# adapter.net
KiCad netlist of a schematic drawn in Altium Designer
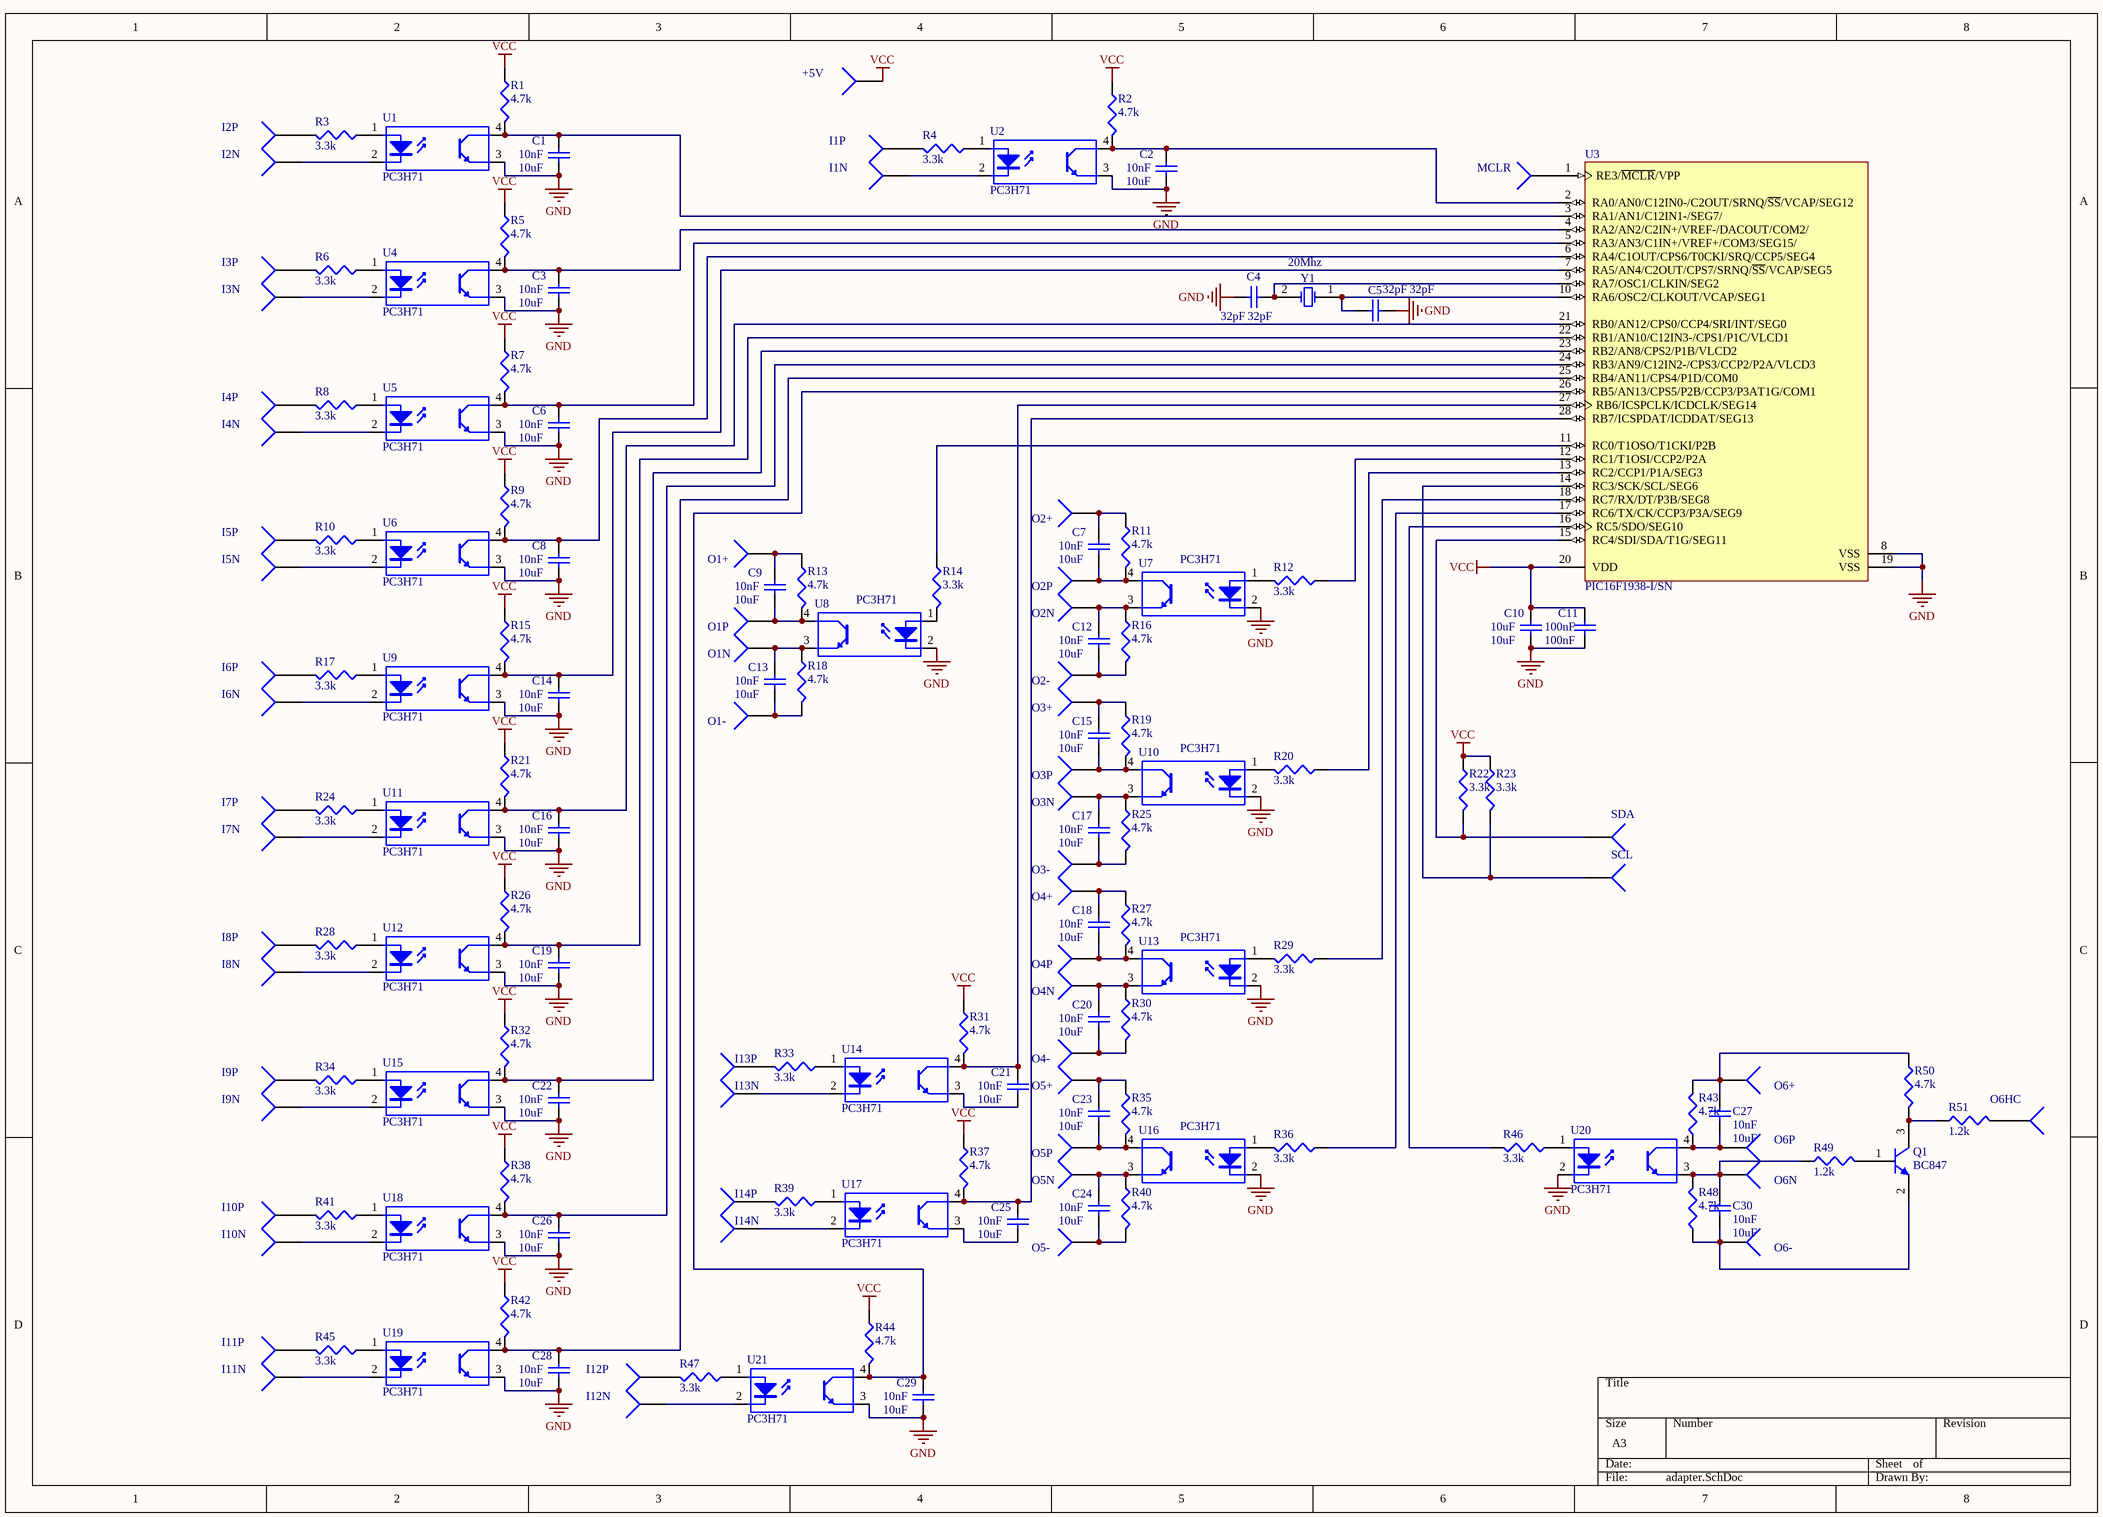
[diagram p0: adapter.SchDoc]

(export (version "E")
  (design (tool "Eeschema 10.0.6"))
  (components
    (comp (ref "+5V")
      (value "IN")
      (footprint "PIN1L")
      (description "Socket")
      (fields (field (name "PUBLISHER") "Altium Limited"))
      (libsource (lib "misc") (part "Socket"))
    )
    (comp (ref "C1")
      (value "10nF")
      (footprint "1608[0603]")
      (description "Capacitor")
      (fields (field (name "ALTIUM_VALUE") "10uF") (field (name "PUBLISHER") "Altium Limited"))
      (libsource (lib "Miscellaneous Devices") (part "Cap"))
    )
    (comp (ref "C2")
      (value "10nF")
      (footprint "1608[0603]")
      (description "Capacitor")
      (fields (field (name "ALTIUM_VALUE") "10uF") (field (name "PUBLISHER") "Altium Limited"))
      (libsource (lib "Miscellaneous Devices") (part "Cap"))
    )
    (comp (ref "C3")
      (value "10nF")
      (footprint "1608[0603]")
      (description "Capacitor")
      (fields (field (name "ALTIUM_VALUE") "10uF") (field (name "PUBLISHER") "Altium Limited"))
      (libsource (lib "Miscellaneous Devices") (part "Cap"))
    )
    (comp (ref "C4")
      (value "32pF")
      (footprint "1608[0603]")
      (description "Capacitor")
      (fields (field (name "ALTIUM_VALUE") "32pF") (field (name "PUBLISHER") "Altium Limited"))
      (libsource (lib "Miscellaneous Devices") (part "Cap"))
    )
    (comp (ref "C5")
      (value "32pF")
      (footprint "1608[0603]")
      (description "Capacitor")
      (fields (field (name "ALTIUM_VALUE") "32pF") (field (name "PUBLISHER") "Altium Limited"))
      (libsource (lib "Miscellaneous Devices") (part "Cap"))
    )
    (comp (ref "C6")
      (value "10nF")
      (footprint "1608[0603]")
      (description "Capacitor")
      (fields (field (name "ALTIUM_VALUE") "10uF") (field (name "PUBLISHER") "Altium Limited"))
      (libsource (lib "Miscellaneous Devices") (part "Cap"))
    )
    (comp (ref "C7")
      (value "10nF")
      (footprint "1608[0603]")
      (description "Capacitor")
      (fields (field (name "ALTIUM_VALUE") "10uF") (field (name "PUBLISHER") "Altium Limited"))
      (libsource (lib "Miscellaneous Devices") (part "Cap"))
    )
    (comp (ref "C8")
      (value "10nF")
      (footprint "1608[0603]")
      (description "Capacitor")
      (fields (field (name "ALTIUM_VALUE") "10uF") (field (name "PUBLISHER") "Altium Limited"))
      (libsource (lib "Miscellaneous Devices") (part "Cap"))
    )
    (comp (ref "C9")
      (value "10nF")
      (footprint "1608[0603]")
      (description "Capacitor")
      (fields (field (name "ALTIUM_VALUE") "10uF") (field (name "PUBLISHER") "Altium Limited"))
      (libsource (lib "Miscellaneous Devices") (part "Cap"))
    )
    (comp (ref "C10")
      (value "10uF")
      (footprint "1608[0603]")
      (description "Capacitor")
      (fields (field (name "ALTIUM_VALUE") "10uF") (field (name "PUBLISHER") "Altium Limited"))
      (libsource (lib "Miscellaneous Devices") (part "Cap"))
    )
    (comp (ref "C11")
      (value "100nF")
      (footprint "1608[0603]")
      (description "Capacitor")
      (fields (field (name "ALTIUM_VALUE") "100nF") (field (name "PUBLISHER") "Altium Limited"))
      (libsource (lib "Miscellaneous Devices") (part "Cap"))
    )
    (comp (ref "C12")
      (value "10nF")
      (footprint "1608[0603]")
      (description "Capacitor")
      (fields (field (name "ALTIUM_VALUE") "10uF") (field (name "PUBLISHER") "Altium Limited"))
      (libsource (lib "Miscellaneous Devices") (part "Cap"))
    )
    (comp (ref "C13")
      (value "10nF")
      (footprint "1608[0603]")
      (description "Capacitor")
      (fields (field (name "ALTIUM_VALUE") "10uF") (field (name "PUBLISHER") "Altium Limited"))
      (libsource (lib "Miscellaneous Devices") (part "Cap"))
    )
    (comp (ref "C14")
      (value "10nF")
      (footprint "1608[0603]")
      (description "Capacitor")
      (fields (field (name "ALTIUM_VALUE") "10uF") (field (name "PUBLISHER") "Altium Limited"))
      (libsource (lib "Miscellaneous Devices") (part "Cap"))
    )
    (comp (ref "C15")
      (value "10nF")
      (footprint "1608[0603]")
      (description "Capacitor")
      (fields (field (name "ALTIUM_VALUE") "10uF") (field (name "PUBLISHER") "Altium Limited"))
      (libsource (lib "Miscellaneous Devices") (part "Cap"))
    )
    (comp (ref "C16")
      (value "10nF")
      (footprint "1608[0603]")
      (description "Capacitor")
      (fields (field (name "ALTIUM_VALUE") "10uF") (field (name "PUBLISHER") "Altium Limited"))
      (libsource (lib "Miscellaneous Devices") (part "Cap"))
    )
    (comp (ref "C17")
      (value "10nF")
      (footprint "1608[0603]")
      (description "Capacitor")
      (fields (field (name "ALTIUM_VALUE") "10uF") (field (name "PUBLISHER") "Altium Limited"))
      (libsource (lib "Miscellaneous Devices") (part "Cap"))
    )
    (comp (ref "C18")
      (value "10nF")
      (footprint "1608[0603]")
      (description "Capacitor")
      (fields (field (name "ALTIUM_VALUE") "10uF") (field (name "PUBLISHER") "Altium Limited"))
      (libsource (lib "Miscellaneous Devices") (part "Cap"))
    )
    (comp (ref "C19")
      (value "10nF")
      (footprint "1608[0603]")
      (description "Capacitor")
      (fields (field (name "ALTIUM_VALUE") "10uF") (field (name "PUBLISHER") "Altium Limited"))
      (libsource (lib "Miscellaneous Devices") (part "Cap"))
    )
    (comp (ref "C20")
      (value "10nF")
      (footprint "1608[0603]")
      (description "Capacitor")
      (fields (field (name "ALTIUM_VALUE") "10uF") (field (name "PUBLISHER") "Altium Limited"))
      (libsource (lib "Miscellaneous Devices") (part "Cap"))
    )
    (comp (ref "C21")
      (value "10nF")
      (footprint "1608[0603]")
      (description "Capacitor")
      (fields (field (name "ALTIUM_VALUE") "10uF") (field (name "PUBLISHER") "Altium Limited"))
      (libsource (lib "Miscellaneous Devices") (part "Cap"))
    )
    (comp (ref "C22")
      (value "10nF")
      (footprint "1608[0603]")
      (description "Capacitor")
      (fields (field (name "ALTIUM_VALUE") "10uF") (field (name "PUBLISHER") "Altium Limited"))
      (libsource (lib "Miscellaneous Devices") (part "Cap"))
    )
    (comp (ref "C23")
      (value "10nF")
      (footprint "1608[0603]")
      (description "Capacitor")
      (fields (field (name "ALTIUM_VALUE") "10uF") (field (name "PUBLISHER") "Altium Limited"))
      (libsource (lib "Miscellaneous Devices") (part "Cap"))
    )
    (comp (ref "C24")
      (value "10nF")
      (footprint "1608[0603]")
      (description "Capacitor")
      (fields (field (name "ALTIUM_VALUE") "10uF") (field (name "PUBLISHER") "Altium Limited"))
      (libsource (lib "Miscellaneous Devices") (part "Cap"))
    )
    (comp (ref "C25")
      (value "10nF")
      (footprint "1608[0603]")
      (description "Capacitor")
      (fields (field (name "ALTIUM_VALUE") "10uF") (field (name "PUBLISHER") "Altium Limited"))
      (libsource (lib "Miscellaneous Devices") (part "Cap"))
    )
    (comp (ref "C26")
      (value "10nF")
      (footprint "1608[0603]")
      (description "Capacitor")
      (fields (field (name "ALTIUM_VALUE") "10uF") (field (name "PUBLISHER") "Altium Limited"))
      (libsource (lib "Miscellaneous Devices") (part "Cap"))
    )
    (comp (ref "C27")
      (value "10nF")
      (footprint "1608[0603]")
      (description "Capacitor")
      (fields (field (name "ALTIUM_VALUE") "10uF") (field (name "PUBLISHER") "Altium Limited"))
      (libsource (lib "Miscellaneous Devices") (part "Cap"))
    )
    (comp (ref "C28")
      (value "10nF")
      (footprint "1608[0603]")
      (description "Capacitor")
      (fields (field (name "ALTIUM_VALUE") "10uF") (field (name "PUBLISHER") "Altium Limited"))
      (libsource (lib "Miscellaneous Devices") (part "Cap"))
    )
    (comp (ref "C29")
      (value "10nF")
      (footprint "1608[0603]")
      (description "Capacitor")
      (fields (field (name "ALTIUM_VALUE") "10uF") (field (name "PUBLISHER") "Altium Limited"))
      (libsource (lib "Miscellaneous Devices") (part "Cap"))
    )
    (comp (ref "C30")
      (value "10nF")
      (footprint "1608[0603]")
      (description "Capacitor")
      (fields (field (name "ALTIUM_VALUE") "10uF") (field (name "PUBLISHER") "Altium Limited"))
      (libsource (lib "Miscellaneous Devices") (part "Cap"))
    )
    (comp (ref "I1N")
      (value "IN")
      (footprint "PIN1L")
      (description "Socket")
      (fields (field (name "PUBLISHER") "Altium Limited"))
      (libsource (lib "misc") (part "Socket"))
    )
    (comp (ref "I1P")
      (value "IN")
      (footprint "PIN1L")
      (description "Socket")
      (fields (field (name "PUBLISHER") "Altium Limited"))
      (libsource (lib "misc") (part "Socket"))
    )
    (comp (ref "I2N")
      (value "IN")
      (footprint "PIN1L")
      (description "Socket")
      (fields (field (name "PUBLISHER") "Altium Limited"))
      (libsource (lib "misc") (part "Socket"))
    )
    (comp (ref "I2P")
      (value "IN")
      (footprint "PIN1L")
      (description "Socket")
      (fields (field (name "PUBLISHER") "Altium Limited"))
      (libsource (lib "misc") (part "Socket"))
    )
    (comp (ref "I3N")
      (value "IN")
      (footprint "PIN1L")
      (description "Socket")
      (fields (field (name "PUBLISHER") "Altium Limited"))
      (libsource (lib "misc") (part "Socket"))
    )
    (comp (ref "I3P")
      (value "IN")
      (footprint "PIN1L")
      (description "Socket")
      (fields (field (name "PUBLISHER") "Altium Limited"))
      (libsource (lib "misc") (part "Socket"))
    )
    (comp (ref "I4N")
      (value "IN")
      (footprint "PIN1L")
      (description "Socket")
      (fields (field (name "PUBLISHER") "Altium Limited"))
      (libsource (lib "misc") (part "Socket"))
    )
    (comp (ref "I4P")
      (value "IN")
      (footprint "PIN1L")
      (description "Socket")
      (fields (field (name "PUBLISHER") "Altium Limited"))
      (libsource (lib "misc") (part "Socket"))
    )
    (comp (ref "I5N")
      (value "IN")
      (footprint "PIN1L")
      (description "Socket")
      (fields (field (name "PUBLISHER") "Altium Limited"))
      (libsource (lib "misc") (part "Socket"))
    )
    (comp (ref "I5P")
      (value "IN")
      (footprint "PIN1L")
      (description "Socket")
      (fields (field (name "PUBLISHER") "Altium Limited"))
      (libsource (lib "misc") (part "Socket"))
    )
    (comp (ref "I6N")
      (value "IN")
      (footprint "PIN1L")
      (description "Socket")
      (fields (field (name "PUBLISHER") "Altium Limited"))
      (libsource (lib "misc") (part "Socket"))
    )
    (comp (ref "I6P")
      (value "IN")
      (footprint "PIN1L")
      (description "Socket")
      (fields (field (name "PUBLISHER") "Altium Limited"))
      (libsource (lib "misc") (part "Socket"))
    )
    (comp (ref "I7N")
      (value "IN")
      (footprint "PIN1L")
      (description "Socket")
      (fields (field (name "PUBLISHER") "Altium Limited"))
      (libsource (lib "misc") (part "Socket"))
    )
    (comp (ref "I7P")
      (value "IN")
      (footprint "PIN1L")
      (description "Socket")
      (fields (field (name "PUBLISHER") "Altium Limited"))
      (libsource (lib "misc") (part "Socket"))
    )
    (comp (ref "I8N")
      (value "IN")
      (footprint "PIN1L")
      (description "Socket")
      (fields (field (name "PUBLISHER") "Altium Limited"))
      (libsource (lib "misc") (part "Socket"))
    )
    (comp (ref "I8P")
      (value "IN")
      (footprint "PIN1L")
      (description "Socket")
      (fields (field (name "PUBLISHER") "Altium Limited"))
      (libsource (lib "misc") (part "Socket"))
    )
    (comp (ref "I9N")
      (value "IN")
      (footprint "PIN1L")
      (description "Socket")
      (fields (field (name "PUBLISHER") "Altium Limited"))
      (libsource (lib "misc") (part "Socket"))
    )
    (comp (ref "I9P")
      (value "IN")
      (footprint "PIN1L")
      (description "Socket")
      (fields (field (name "PUBLISHER") "Altium Limited"))
      (libsource (lib "misc") (part "Socket"))
    )
    (comp (ref "I10N")
      (value "IN")
      (footprint "PIN1L")
      (description "Socket")
      (fields (field (name "PUBLISHER") "Altium Limited"))
      (libsource (lib "misc") (part "Socket"))
    )
    (comp (ref "I10P")
      (value "IN")
      (footprint "PIN1L")
      (description "Socket")
      (fields (field (name "PUBLISHER") "Altium Limited"))
      (libsource (lib "misc") (part "Socket"))
    )
    (comp (ref "I11N")
      (value "IN")
      (footprint "PIN1L")
      (description "Socket")
      (fields (field (name "PUBLISHER") "Altium Limited"))
      (libsource (lib "misc") (part "Socket"))
    )
    (comp (ref "I11P")
      (value "IN")
      (footprint "PIN1L")
      (description "Socket")
      (fields (field (name "PUBLISHER") "Altium Limited"))
      (libsource (lib "misc") (part "Socket"))
    )
    (comp (ref "I12N")
      (value "IN")
      (footprint "PIN1L")
      (description "Socket")
      (fields (field (name "PUBLISHER") "Altium Limited"))
      (libsource (lib "misc") (part "Socket"))
    )
    (comp (ref "I12P")
      (value "IN")
      (footprint "PIN1L")
      (description "Socket")
      (fields (field (name "PUBLISHER") "Altium Limited"))
      (libsource (lib "misc") (part "Socket"))
    )
    (comp (ref "I13N")
      (value "IN")
      (footprint "PIN1L")
      (description "Socket")
      (fields (field (name "PUBLISHER") "Altium Limited"))
      (libsource (lib "misc") (part "Socket"))
    )
    (comp (ref "I13P")
      (value "IN")
      (footprint "PIN1L")
      (description "Socket")
      (fields (field (name "PUBLISHER") "Altium Limited"))
      (libsource (lib "misc") (part "Socket"))
    )
    (comp (ref "I14N")
      (value "IN")
      (footprint "PIN1L")
      (description "Socket")
      (fields (field (name "PUBLISHER") "Altium Limited"))
      (libsource (lib "misc") (part "Socket"))
    )
    (comp (ref "I14P")
      (value "IN")
      (footprint "PIN1L")
      (description "Socket")
      (fields (field (name "PUBLISHER") "Altium Limited"))
      (libsource (lib "misc") (part "Socket"))
    )
    (comp (ref "MCLR")
      (value "IN")
      (footprint "PIN1L")
      (description "Socket")
      (fields (field (name "PUBLISHER") "Altium Limited"))
      (libsource (lib "misc") (part "Socket"))
    )
    (comp (ref "O1+")
      (value "SDA")
      (footprint "PIN1L")
      (description "Socket")
      (fields (field (name "PUBLISHER") "Altium Limited"))
      (libsource (lib "misc") (part "Socket"))
    )
    (comp (ref "O1-")
      (value "SDA")
      (footprint "PIN1L")
      (description "Socket")
      (fields (field (name "PUBLISHER") "Altium Limited"))
      (libsource (lib "misc") (part "Socket"))
    )
    (comp (ref "O1N")
      (value "SDA")
      (footprint "PIN1L")
      (description "Socket")
      (fields (field (name "PUBLISHER") "Altium Limited"))
      (libsource (lib "misc") (part "Socket"))
    )
    (comp (ref "O1P")
      (value "SDA")
      (footprint "PIN1L")
      (description "Socket")
      (fields (field (name "PUBLISHER") "Altium Limited"))
      (libsource (lib "misc") (part "Socket"))
    )
    (comp (ref "O2+")
      (value "SDA")
      (footprint "PIN1L")
      (description "Socket")
      (fields (field (name "PUBLISHER") "Altium Limited"))
      (libsource (lib "misc") (part "Socket"))
    )
    (comp (ref "O2-")
      (value "SDA")
      (footprint "PIN1L")
      (description "Socket")
      (fields (field (name "PUBLISHER") "Altium Limited"))
      (libsource (lib "misc") (part "Socket"))
    )
    (comp (ref "O2N")
      (value "SDA")
      (footprint "PIN1L")
      (description "Socket")
      (fields (field (name "PUBLISHER") "Altium Limited"))
      (libsource (lib "misc") (part "Socket"))
    )
    (comp (ref "O2P")
      (value "SDA")
      (footprint "PIN1L")
      (description "Socket")
      (fields (field (name "PUBLISHER") "Altium Limited"))
      (libsource (lib "misc") (part "Socket"))
    )
    (comp (ref "O3+")
      (value "SDA")
      (footprint "PIN1L")
      (description "Socket")
      (fields (field (name "PUBLISHER") "Altium Limited"))
      (libsource (lib "misc") (part "Socket"))
    )
    (comp (ref "O3-")
      (value "SDA")
      (footprint "PIN1L")
      (description "Socket")
      (fields (field (name "PUBLISHER") "Altium Limited"))
      (libsource (lib "misc") (part "Socket"))
    )
    (comp (ref "O3N")
      (value "SDA")
      (footprint "PIN1L")
      (description "Socket")
      (fields (field (name "PUBLISHER") "Altium Limited"))
      (libsource (lib "misc") (part "Socket"))
    )
    (comp (ref "O3P")
      (value "SDA")
      (footprint "PIN1L")
      (description "Socket")
      (fields (field (name "PUBLISHER") "Altium Limited"))
      (libsource (lib "misc") (part "Socket"))
    )
    (comp (ref "O4+")
      (value "SDA")
      (footprint "PIN1L")
      (description "Socket")
      (fields (field (name "PUBLISHER") "Altium Limited"))
      (libsource (lib "misc") (part "Socket"))
    )
    (comp (ref "O4-")
      (value "SDA")
      (footprint "PIN1L")
      (description "Socket")
      (fields (field (name "PUBLISHER") "Altium Limited"))
      (libsource (lib "misc") (part "Socket"))
    )
    (comp (ref "O4N")
      (value "SDA")
      (footprint "PIN1L")
      (description "Socket")
      (fields (field (name "PUBLISHER") "Altium Limited"))
      (libsource (lib "misc") (part "Socket"))
    )
    (comp (ref "O4P")
      (value "SDA")
      (footprint "PIN1L")
      (description "Socket")
      (fields (field (name "PUBLISHER") "Altium Limited"))
      (libsource (lib "misc") (part "Socket"))
    )
    (comp (ref "O5+")
      (value "SDA")
      (footprint "PIN1L")
      (description "Socket")
      (fields (field (name "PUBLISHER") "Altium Limited"))
      (libsource (lib "misc") (part "Socket"))
    )
    (comp (ref "O5-")
      (value "SDA")
      (footprint "PIN1L")
      (description "Socket")
      (fields (field (name "PUBLISHER") "Altium Limited"))
      (libsource (lib "misc") (part "Socket"))
    )
    (comp (ref "O5N")
      (value "SDA")
      (footprint "PIN1L")
      (description "Socket")
      (fields (field (name "PUBLISHER") "Altium Limited"))
      (libsource (lib "misc") (part "Socket"))
    )
    (comp (ref "O5P")
      (value "SDA")
      (footprint "PIN1L")
      (description "Socket")
      (fields (field (name "PUBLISHER") "Altium Limited"))
      (libsource (lib "misc") (part "Socket"))
    )
    (comp (ref "O6+")
      (value "SDA")
      (footprint "PIN1L")
      (description "Socket")
      (fields (field (name "PUBLISHER") "Altium Limited"))
      (libsource (lib "misc") (part "Socket"))
    )
    (comp (ref "O6-")
      (value "SDA")
      (footprint "PIN1L")
      (description "Socket")
      (fields (field (name "PUBLISHER") "Altium Limited"))
      (libsource (lib "misc") (part "Socket"))
    )
    (comp (ref "O6HC")
      (value "SDA")
      (footprint "PIN1L")
      (description "Socket")
      (fields (field (name "PUBLISHER") "Altium Limited"))
      (libsource (lib "misc") (part "Socket"))
    )
    (comp (ref "O6N")
      (value "SDA")
      (footprint "PIN1L")
      (description "Socket")
      (fields (field (name "PUBLISHER") "Altium Limited"))
      (libsource (lib "misc") (part "Socket"))
    )
    (comp (ref "O6P")
      (value "SDA")
      (footprint "PIN1L")
      (description "Socket")
      (fields (field (name "PUBLISHER") "Altium Limited"))
      (libsource (lib "misc") (part "Socket"))
    )
    (comp (ref "Q1")
      (value "BC847")
      (footprint "SOT-23_N")
      (description "NPN Bipolar Transistor")
      (fields (field (name "PUBLISHER") "Altium Limited"))
      (libsource (lib "Miscellaneous Devices") (part "NPN"))
    )
    (comp (ref "R1")
      (value "4.7k")
      (footprint "J1-0603")
      (description "Resistor")
      (fields (field (name "PUBLISHER") "Altium Limited"))
      (libsource (lib "Miscellaneous Devices") (part "Res3"))
    )
    (comp (ref "R2")
      (value "4.7k")
      (footprint "J1-0603")
      (description "Resistor")
      (fields (field (name "PUBLISHER") "Altium Limited"))
      (libsource (lib "Miscellaneous Devices") (part "Res3"))
    )
    (comp (ref "R3")
      (value "3.3k")
      (footprint "J1-0603")
      (description "Resistor")
      (fields (field (name "PUBLISHER") "Altium Limited"))
      (libsource (lib "Miscellaneous Devices") (part "Res3"))
    )
    (comp (ref "R4")
      (value "3.3k")
      (footprint "J1-0603")
      (description "Resistor")
      (fields (field (name "PUBLISHER") "Altium Limited"))
      (libsource (lib "Miscellaneous Devices") (part "Res3"))
    )
    (comp (ref "R5")
      (value "4.7k")
      (footprint "J1-0603")
      (description "Resistor")
      (fields (field (name "PUBLISHER") "Altium Limited"))
      (libsource (lib "Miscellaneous Devices") (part "Res3"))
    )
    (comp (ref "R6")
      (value "3.3k")
      (footprint "J1-0603")
      (description "Resistor")
      (fields (field (name "PUBLISHER") "Altium Limited"))
      (libsource (lib "Miscellaneous Devices") (part "Res3"))
    )
    (comp (ref "R7")
      (value "4.7k")
      (footprint "J1-0603")
      (description "Resistor")
      (fields (field (name "PUBLISHER") "Altium Limited"))
      (libsource (lib "Miscellaneous Devices") (part "Res3"))
    )
    (comp (ref "R8")
      (value "3.3k")
      (footprint "J1-0603")
      (description "Resistor")
      (fields (field (name "PUBLISHER") "Altium Limited"))
      (libsource (lib "Miscellaneous Devices") (part "Res3"))
    )
    (comp (ref "R9")
      (value "4.7k")
      (footprint "J1-0603")
      (description "Resistor")
      (fields (field (name "PUBLISHER") "Altium Limited"))
      (libsource (lib "Miscellaneous Devices") (part "Res3"))
    )
    (comp (ref "R10")
      (value "3.3k")
      (footprint "J1-0603")
      (description "Resistor")
      (fields (field (name "PUBLISHER") "Altium Limited"))
      (libsource (lib "Miscellaneous Devices") (part "Res3"))
    )
    (comp (ref "R11")
      (value "4.7k")
      (footprint "J1-0603")
      (description "Resistor")
      (fields (field (name "PUBLISHER") "Altium Limited"))
      (libsource (lib "Miscellaneous Devices") (part "Res3"))
    )
    (comp (ref "R12")
      (value "3.3k")
      (footprint "J1-0603")
      (description "Resistor")
      (fields (field (name "PUBLISHER") "Altium Limited"))
      (libsource (lib "Miscellaneous Devices") (part "Res3"))
    )
    (comp (ref "R13")
      (value "4.7k")
      (footprint "J1-0603")
      (description "Resistor")
      (fields (field (name "PUBLISHER") "Altium Limited"))
      (libsource (lib "Miscellaneous Devices") (part "Res3"))
    )
    (comp (ref "R14")
      (value "3.3k")
      (footprint "J1-0603")
      (description "Resistor")
      (fields (field (name "PUBLISHER") "Altium Limited"))
      (libsource (lib "Miscellaneous Devices") (part "Res3"))
    )
    (comp (ref "R15")
      (value "4.7k")
      (footprint "J1-0603")
      (description "Resistor")
      (fields (field (name "PUBLISHER") "Altium Limited"))
      (libsource (lib "Miscellaneous Devices") (part "Res3"))
    )
    (comp (ref "R16")
      (value "4.7k")
      (footprint "J1-0603")
      (description "Resistor")
      (fields (field (name "PUBLISHER") "Altium Limited"))
      (libsource (lib "Miscellaneous Devices") (part "Res3"))
    )
    (comp (ref "R17")
      (value "3.3k")
      (footprint "J1-0603")
      (description "Resistor")
      (fields (field (name "PUBLISHER") "Altium Limited"))
      (libsource (lib "Miscellaneous Devices") (part "Res3"))
    )
    (comp (ref "R18")
      (value "4.7k")
      (footprint "J1-0603")
      (description "Resistor")
      (fields (field (name "PUBLISHER") "Altium Limited"))
      (libsource (lib "Miscellaneous Devices") (part "Res3"))
    )
    (comp (ref "R19")
      (value "4.7k")
      (footprint "J1-0603")
      (description "Resistor")
      (fields (field (name "PUBLISHER") "Altium Limited"))
      (libsource (lib "Miscellaneous Devices") (part "Res3"))
    )
    (comp (ref "R20")
      (value "3.3k")
      (footprint "J1-0603")
      (description "Resistor")
      (fields (field (name "PUBLISHER") "Altium Limited"))
      (libsource (lib "Miscellaneous Devices") (part "Res3"))
    )
    (comp (ref "R21")
      (value "4.7k")
      (footprint "J1-0603")
      (description "Resistor")
      (fields (field (name "PUBLISHER") "Altium Limited"))
      (libsource (lib "Miscellaneous Devices") (part "Res3"))
    )
    (comp (ref "R22")
      (value "3.3k")
      (footprint "J1-0603")
      (description "Resistor")
      (fields (field (name "PUBLISHER") "Altium Limited"))
      (libsource (lib "Miscellaneous Devices") (part "Res3"))
    )
    (comp (ref "R23")
      (value "3.3k")
      (footprint "J1-0603")
      (description "Resistor")
      (fields (field (name "PUBLISHER") "Altium Limited"))
      (libsource (lib "Miscellaneous Devices") (part "Res3"))
    )
    (comp (ref "R24")
      (value "3.3k")
      (footprint "J1-0603")
      (description "Resistor")
      (fields (field (name "PUBLISHER") "Altium Limited"))
      (libsource (lib "Miscellaneous Devices") (part "Res3"))
    )
    (comp (ref "R25")
      (value "4.7k")
      (footprint "J1-0603")
      (description "Resistor")
      (fields (field (name "PUBLISHER") "Altium Limited"))
      (libsource (lib "Miscellaneous Devices") (part "Res3"))
    )
    (comp (ref "R26")
      (value "4.7k")
      (footprint "J1-0603")
      (description "Resistor")
      (fields (field (name "PUBLISHER") "Altium Limited"))
      (libsource (lib "Miscellaneous Devices") (part "Res3"))
    )
    (comp (ref "R27")
      (value "4.7k")
      (footprint "J1-0603")
      (description "Resistor")
      (fields (field (name "PUBLISHER") "Altium Limited"))
      (libsource (lib "Miscellaneous Devices") (part "Res3"))
    )
    (comp (ref "R28")
      (value "3.3k")
      (footprint "J1-0603")
      (description "Resistor")
      (fields (field (name "PUBLISHER") "Altium Limited"))
      (libsource (lib "Miscellaneous Devices") (part "Res3"))
    )
    (comp (ref "R29")
      (value "3.3k")
      (footprint "J1-0603")
      (description "Resistor")
      (fields (field (name "PUBLISHER") "Altium Limited"))
      (libsource (lib "Miscellaneous Devices") (part "Res3"))
    )
    (comp (ref "R30")
      (value "4.7k")
      (footprint "J1-0603")
      (description "Resistor")
      (fields (field (name "PUBLISHER") "Altium Limited"))
      (libsource (lib "Miscellaneous Devices") (part "Res3"))
    )
    (comp (ref "R31")
      (value "4.7k")
      (footprint "J1-0603")
      (description "Resistor")
      (fields (field (name "PUBLISHER") "Altium Limited"))
      (libsource (lib "Miscellaneous Devices") (part "Res3"))
    )
    (comp (ref "R32")
      (value "4.7k")
      (footprint "J1-0603")
      (description "Resistor")
      (fields (field (name "PUBLISHER") "Altium Limited"))
      (libsource (lib "Miscellaneous Devices") (part "Res3"))
    )
    (comp (ref "R33")
      (value "3.3k")
      (footprint "J1-0603")
      (description "Resistor")
      (fields (field (name "PUBLISHER") "Altium Limited"))
      (libsource (lib "Miscellaneous Devices") (part "Res3"))
    )
    (comp (ref "R34")
      (value "3.3k")
      (footprint "J1-0603")
      (description "Resistor")
      (fields (field (name "PUBLISHER") "Altium Limited"))
      (libsource (lib "Miscellaneous Devices") (part "Res3"))
    )
    (comp (ref "R35")
      (value "4.7k")
      (footprint "J1-0603")
      (description "Resistor")
      (fields (field (name "PUBLISHER") "Altium Limited"))
      (libsource (lib "Miscellaneous Devices") (part "Res3"))
    )
    (comp (ref "R36")
      (value "3.3k")
      (footprint "J1-0603")
      (description "Resistor")
      (fields (field (name "PUBLISHER") "Altium Limited"))
      (libsource (lib "Miscellaneous Devices") (part "Res3"))
    )
    (comp (ref "R37")
      (value "4.7k")
      (footprint "J1-0603")
      (description "Resistor")
      (fields (field (name "PUBLISHER") "Altium Limited"))
      (libsource (lib "Miscellaneous Devices") (part "Res3"))
    )
    (comp (ref "R38")
      (value "4.7k")
      (footprint "J1-0603")
      (description "Resistor")
      (fields (field (name "PUBLISHER") "Altium Limited"))
      (libsource (lib "Miscellaneous Devices") (part "Res3"))
    )
    (comp (ref "R39")
      (value "3.3k")
      (footprint "J1-0603")
      (description "Resistor")
      (fields (field (name "PUBLISHER") "Altium Limited"))
      (libsource (lib "Miscellaneous Devices") (part "Res3"))
    )
    (comp (ref "R40")
      (value "4.7k")
      (footprint "J1-0603")
      (description "Resistor")
      (fields (field (name "PUBLISHER") "Altium Limited"))
      (libsource (lib "Miscellaneous Devices") (part "Res3"))
    )
    (comp (ref "R41")
      (value "3.3k")
      (footprint "J1-0603")
      (description "Resistor")
      (fields (field (name "PUBLISHER") "Altium Limited"))
      (libsource (lib "Miscellaneous Devices") (part "Res3"))
    )
    (comp (ref "R42")
      (value "4.7k")
      (footprint "J1-0603")
      (description "Resistor")
      (fields (field (name "PUBLISHER") "Altium Limited"))
      (libsource (lib "Miscellaneous Devices") (part "Res3"))
    )
    (comp (ref "R43")
      (value "4.7k")
      (footprint "J1-0603")
      (description "Resistor")
      (fields (field (name "PUBLISHER") "Altium Limited"))
      (libsource (lib "Miscellaneous Devices") (part "Res3"))
    )
    (comp (ref "R44")
      (value "4.7k")
      (footprint "J1-0603")
      (description "Resistor")
      (fields (field (name "PUBLISHER") "Altium Limited"))
      (libsource (lib "Miscellaneous Devices") (part "Res3"))
    )
    (comp (ref "R45")
      (value "3.3k")
      (footprint "J1-0603")
      (description "Resistor")
      (fields (field (name "PUBLISHER") "Altium Limited"))
      (libsource (lib "Miscellaneous Devices") (part "Res3"))
    )
    (comp (ref "R46")
      (value "3.3k")
      (footprint "J1-0603")
      (description "Resistor")
      (fields (field (name "PUBLISHER") "Altium Limited"))
      (libsource (lib "Miscellaneous Devices") (part "Res3"))
    )
    (comp (ref "R47")
      (value "3.3k")
      (footprint "J1-0603")
      (description "Resistor")
      (fields (field (name "PUBLISHER") "Altium Limited"))
      (libsource (lib "Miscellaneous Devices") (part "Res3"))
    )
    (comp (ref "R48")
      (value "4.7k")
      (footprint "J1-0603")
      (description "Resistor")
      (fields (field (name "PUBLISHER") "Altium Limited"))
      (libsource (lib "Miscellaneous Devices") (part "Res3"))
    )
    (comp (ref "R49")
      (value "1.2k")
      (footprint "J1-0603")
      (description "Resistor")
      (fields (field (name "PUBLISHER") "Altium Limited"))
      (libsource (lib "Miscellaneous Devices") (part "Res3"))
    )
    (comp (ref "R50")
      (value "4.7k")
      (footprint "J1-0603")
      (description "Resistor")
      (fields (field (name "PUBLISHER") "Altium Limited"))
      (libsource (lib "Miscellaneous Devices") (part "Res3"))
    )
    (comp (ref "R51")
      (value "1.2k")
      (footprint "J1-0603")
      (description "Resistor")
      (fields (field (name "PUBLISHER") "Altium Limited"))
      (libsource (lib "Miscellaneous Devices") (part "Res3"))
    )
    (comp (ref "SCL")
      (value "SCL")
      (footprint "PIN1L")
      (description "Socket")
      (fields (field (name "PUBLISHER") "Altium Limited"))
      (libsource (lib "misc") (part "Socket"))
    )
    (comp (ref "SDA")
      (value "SDA")
      (footprint "PIN1L")
      (description "Socket")
      (fields (field (name "PUBLISHER") "Altium Limited"))
      (libsource (lib "misc") (part "Socket"))
    )
    (comp (ref "U1")
      (value "PC3H71")
      (footprint "PC3H71")
      (description "4-Pin Phototransistor Optocoupler")
      (fields (field (name "PUBLISHER") "Altium Limited"))
      (libsource (lib "Miscellaneous Devices") (part "Optoisolator1"))
    )
    (comp (ref "U2")
      (value "PC3H71")
      (footprint "PC3H71")
      (description "4-Pin Phototransistor Optocoupler")
      (fields (field (name "PUBLISHER") "Altium Limited"))
      (libsource (lib "Miscellaneous Devices") (part "Optoisolator1"))
    )
    (comp (ref "U3")
      (value "PIC16F1938-I/SN")
      (footprint "SOIC-SO28_N")
      (fields (field (name "PUBLISHER") "Altium Limited"))
      (libsource (lib "Microchip Microcontroller 8-Bit PIC16") (part "PIC16F1936-I/SO"))
    )
    (comp (ref "U4")
      (value "PC3H71")
      (footprint "PC3H71")
      (description "4-Pin Phototransistor Optocoupler")
      (fields (field (name "PUBLISHER") "Altium Limited"))
      (libsource (lib "Miscellaneous Devices") (part "Optoisolator1"))
    )
    (comp (ref "U5")
      (value "PC3H71")
      (footprint "PC3H71")
      (description "4-Pin Phototransistor Optocoupler")
      (fields (field (name "PUBLISHER") "Altium Limited"))
      (libsource (lib "Miscellaneous Devices") (part "Optoisolator1"))
    )
    (comp (ref "U6")
      (value "PC3H71")
      (footprint "PC3H71")
      (description "4-Pin Phototransistor Optocoupler")
      (fields (field (name "PUBLISHER") "Altium Limited"))
      (libsource (lib "Miscellaneous Devices") (part "Optoisolator1"))
    )
    (comp (ref "U7")
      (value "PC3H71")
      (footprint "PC3H71")
      (description "4-Pin Phototransistor Optocoupler")
      (fields (field (name "PUBLISHER") "Altium Limited"))
      (libsource (lib "Miscellaneous Devices") (part "Optoisolator1"))
    )
    (comp (ref "U8")
      (value "PC3H71")
      (footprint "PC3H71")
      (description "4-Pin Phototransistor Optocoupler")
      (fields (field (name "PUBLISHER") "Altium Limited"))
      (libsource (lib "Miscellaneous Devices") (part "Optoisolator1"))
    )
    (comp (ref "U9")
      (value "PC3H71")
      (footprint "PC3H71")
      (description "4-Pin Phototransistor Optocoupler")
      (fields (field (name "PUBLISHER") "Altium Limited"))
      (libsource (lib "Miscellaneous Devices") (part "Optoisolator1"))
    )
    (comp (ref "U10")
      (value "PC3H71")
      (footprint "PC3H71")
      (description "4-Pin Phototransistor Optocoupler")
      (fields (field (name "PUBLISHER") "Altium Limited"))
      (libsource (lib "Miscellaneous Devices") (part "Optoisolator1"))
    )
    (comp (ref "U11")
      (value "PC3H71")
      (footprint "PC3H71")
      (description "4-Pin Phototransistor Optocoupler")
      (fields (field (name "PUBLISHER") "Altium Limited"))
      (libsource (lib "Miscellaneous Devices") (part "Optoisolator1"))
    )
    (comp (ref "U12")
      (value "PC3H71")
      (footprint "PC3H71")
      (description "4-Pin Phototransistor Optocoupler")
      (fields (field (name "PUBLISHER") "Altium Limited"))
      (libsource (lib "Miscellaneous Devices") (part "Optoisolator1"))
    )
    (comp (ref "U13")
      (value "PC3H71")
      (footprint "PC3H71")
      (description "4-Pin Phototransistor Optocoupler")
      (fields (field (name "PUBLISHER") "Altium Limited"))
      (libsource (lib "Miscellaneous Devices") (part "Optoisolator1"))
    )
    (comp (ref "U14")
      (value "PC3H71")
      (footprint "PC3H71")
      (description "4-Pin Phototransistor Optocoupler")
      (fields (field (name "PUBLISHER") "Altium Limited"))
      (libsource (lib "Miscellaneous Devices") (part "Optoisolator1"))
    )
    (comp (ref "U15")
      (value "PC3H71")
      (footprint "PC3H71")
      (description "4-Pin Phototransistor Optocoupler")
      (fields (field (name "PUBLISHER") "Altium Limited"))
      (libsource (lib "Miscellaneous Devices") (part "Optoisolator1"))
    )
    (comp (ref "U16")
      (value "PC3H71")
      (footprint "PC3H71")
      (description "4-Pin Phototransistor Optocoupler")
      (fields (field (name "PUBLISHER") "Altium Limited"))
      (libsource (lib "Miscellaneous Devices") (part "Optoisolator1"))
    )
    (comp (ref "U17")
      (value "PC3H71")
      (footprint "PC3H71")
      (description "4-Pin Phototransistor Optocoupler")
      (fields (field (name "PUBLISHER") "Altium Limited"))
      (libsource (lib "Miscellaneous Devices") (part "Optoisolator1"))
    )
    (comp (ref "U18")
      (value "PC3H71")
      (footprint "PC3H71")
      (description "4-Pin Phototransistor Optocoupler")
      (fields (field (name "PUBLISHER") "Altium Limited"))
      (libsource (lib "Miscellaneous Devices") (part "Optoisolator1"))
    )
    (comp (ref "U19")
      (value "PC3H71")
      (footprint "PC3H71")
      (description "4-Pin Phototransistor Optocoupler")
      (fields (field (name "PUBLISHER") "Altium Limited"))
      (libsource (lib "Miscellaneous Devices") (part "Optoisolator1"))
    )
    (comp (ref "U20")
      (value "PC3H71")
      (footprint "PC3H71")
      (description "4-Pin Phototransistor Optocoupler")
      (fields (field (name "PUBLISHER") "Altium Limited"))
      (libsource (lib "Miscellaneous Devices") (part "Optoisolator1"))
    )
    (comp (ref "U21")
      (value "PC3H71")
      (footprint "PC3H71")
      (description "4-Pin Phototransistor Optocoupler")
      (fields (field (name "PUBLISHER") "Altium Limited"))
      (libsource (lib "Miscellaneous Devices") (part "Optoisolator1"))
    )
    (comp (ref "Y1")
      (value "20Mhz")
      (footprint "XTAL")
      (description "Crystal Oscillator")
      (fields (field (name "PUBLISHER") "Altium Limited"))
      (libsource (lib "Miscellaneous Devices") (part "XTAL"))
    )
  )
  (nets
    (net (code "1") (name "GND") (class "Default")
      (node (ref "C1") (pin "1") (pinfunction "1_1") (pintype "passive"))
      (node (ref "C10") (pin "1") (pinfunction "1_1") (pintype "passive"))
      (node (ref "C11") (pin "1") (pinfunction "1_1") (pintype "passive"))
      (node (ref "C14") (pin "1") (pinfunction "1_1") (pintype "passive"))
      (node (ref "C16") (pin "1") (pinfunction "1_1") (pintype "passive"))
      (node (ref "C19") (pin "1") (pinfunction "1_1") (pintype "passive"))
      (node (ref "C2") (pin "1") (pinfunction "1_1") (pintype "passive"))
      (node (ref "C22") (pin "1") (pinfunction "1_1") (pintype "passive"))
      (node (ref "C26") (pin "1") (pinfunction "1_1") (pintype "passive"))
      (node (ref "C28") (pin "1") (pinfunction "1_1") (pintype "passive"))
      (node (ref "C29") (pin "1") (pinfunction "1_1") (pintype "passive"))
      (node (ref "C3") (pin "1") (pinfunction "1_1") (pintype "passive"))
      (node (ref "C4") (pin "1") (pinfunction "1_1") (pintype "passive"))
      (node (ref "C5") (pin "2") (pinfunction "2_2") (pintype "passive"))
      (node (ref "C6") (pin "1") (pinfunction "1_1") (pintype "passive"))
      (node (ref "C8") (pin "1") (pinfunction "1_1") (pintype "passive"))
      (node (ref "U1") (pin "3") (pinfunction "E_3") (pintype "passive"))
      (node (ref "U10") (pin "2") (pinfunction "K_2") (pintype "passive"))
      (node (ref "U11") (pin "3") (pinfunction "E_3") (pintype "passive"))
      (node (ref "U12") (pin "3") (pinfunction "E_3") (pintype "passive"))
      (node (ref "U13") (pin "2") (pinfunction "K_2") (pintype "passive"))
      (node (ref "U15") (pin "3") (pinfunction "E_3") (pintype "passive"))
      (node (ref "U16") (pin "2") (pinfunction "K_2") (pintype "passive"))
      (node (ref "U18") (pin "3") (pinfunction "E_3") (pintype "passive"))
      (node (ref "U19") (pin "3") (pinfunction "E_3") (pintype "passive"))
      (node (ref "U2") (pin "3") (pinfunction "E_3") (pintype "passive"))
      (node (ref "U20") (pin "2") (pinfunction "K_2") (pintype "passive"))
      (node (ref "U21") (pin "3") (pinfunction "E_3") (pintype "passive"))
      (node (ref "U3") (pin "19") (pinfunction "VSS_19") (pintype "power_in"))
      (node (ref "U3") (pin "8") (pinfunction "VSS_8") (pintype "power_in"))
      (node (ref "U4") (pin "3") (pinfunction "E_3") (pintype "passive"))
      (node (ref "U5") (pin "3") (pinfunction "E_3") (pintype "passive"))
      (node (ref "U6") (pin "3") (pinfunction "E_3") (pintype "passive"))
      (node (ref "U7") (pin "2") (pinfunction "K_2") (pintype "passive"))
      (node (ref "U8") (pin "2") (pinfunction "K_2") (pintype "passive"))
      (node (ref "U9") (pin "3") (pinfunction "E_3") (pintype "passive"))
    )
    (net (code "2") (name "Net-(C7-Pad2)") (class "Default")
      (node (ref "C7") (pin "2") (pinfunction "2_2") (pintype "passive"))
      (node (ref "O2+") (pin "1") (pinfunction "1_1") (pintype "passive"))
      (node (ref "R11") (pin "1") (pinfunction "1_1") (pintype "passive"))
    )
    (net (code "3") (name "Net-(C9-Pad2)") (class "Default")
      (node (ref "C9") (pin "2") (pinfunction "2_2") (pintype "passive"))
      (node (ref "O1+") (pin "1") (pinfunction "1_1") (pintype "passive"))
      (node (ref "R13") (pin "1") (pinfunction "1_1") (pintype "passive"))
    )
    (net (code "4") (name "Net-(C12-Pad1)") (class "Default")
      (node (ref "C12") (pin "1") (pinfunction "1_1") (pintype "passive"))
      (node (ref "O2-") (pin "1") (pinfunction "1_1") (pintype "passive"))
      (node (ref "R16") (pin "2") (pinfunction "2_2") (pintype "passive"))
    )
    (net (code "5") (name "Net-(C13-Pad1)") (class "Default")
      (node (ref "C13") (pin "1") (pinfunction "1_1") (pintype "passive"))
      (node (ref "O1-") (pin "1") (pinfunction "1_1") (pintype "passive"))
      (node (ref "R18") (pin "2") (pinfunction "2_2") (pintype "passive"))
    )
    (net (code "6") (name "Net-(C15-Pad2)") (class "Default")
      (node (ref "C15") (pin "2") (pinfunction "2_2") (pintype "passive"))
      (node (ref "O3+") (pin "1") (pinfunction "1_1") (pintype "passive"))
      (node (ref "R19") (pin "1") (pinfunction "1_1") (pintype "passive"))
    )
    (net (code "7") (name "Net-(C17-Pad1)") (class "Default")
      (node (ref "C17") (pin "1") (pinfunction "1_1") (pintype "passive"))
      (node (ref "O3-") (pin "1") (pinfunction "1_1") (pintype "passive"))
      (node (ref "R25") (pin "2") (pinfunction "2_2") (pintype "passive"))
    )
    (net (code "8") (name "Net-(C18-Pad2)") (class "Default")
      (node (ref "C18") (pin "2") (pinfunction "2_2") (pintype "passive"))
      (node (ref "O4+") (pin "1") (pinfunction "1_1") (pintype "passive"))
      (node (ref "R27") (pin "1") (pinfunction "1_1") (pintype "passive"))
    )
    (net (code "9") (name "Net-(C20-Pad1)") (class "Default")
      (node (ref "C20") (pin "1") (pinfunction "1_1") (pintype "passive"))
      (node (ref "O4-") (pin "1") (pinfunction "1_1") (pintype "passive"))
      (node (ref "R30") (pin "2") (pinfunction "2_2") (pintype "passive"))
    )
    (net (code "10") (name "Net-(C23-Pad2)") (class "Default")
      (node (ref "C23") (pin "2") (pinfunction "2_2") (pintype "passive"))
      (node (ref "O5+") (pin "1") (pinfunction "1_1") (pintype "passive"))
      (node (ref "R35") (pin "1") (pinfunction "1_1") (pintype "passive"))
    )
    (net (code "11") (name "Net-(C24-Pad1)") (class "Default")
      (node (ref "C24") (pin "1") (pinfunction "1_1") (pintype "passive"))
      (node (ref "O5-") (pin "1") (pinfunction "1_1") (pintype "passive"))
      (node (ref "R40") (pin "2") (pinfunction "2_2") (pintype "passive"))
    )
    (net (code "12") (name "Net-(C27-Pad2)") (class "Default")
      (node (ref "C27") (pin "2") (pinfunction "2_2") (pintype "passive"))
      (node (ref "O6+") (pin "1") (pinfunction "1_1") (pintype "passive"))
      (node (ref "R43") (pin "1") (pinfunction "1_1") (pintype "passive"))
      (node (ref "R50") (pin "1") (pinfunction "1_1") (pintype "passive"))
    )
    (net (code "13") (name "Net-(I1P-Pad1)") (class "Default")
      (node (ref "I1P") (pin "1") (pinfunction "1_1") (pintype "passive"))
      (node (ref "R4") (pin "2") (pinfunction "2_2") (pintype "passive"))
    )
    (net (code "14") (name "Net-(I2P-Pad1)") (class "Default")
      (node (ref "I2P") (pin "1") (pinfunction "1_1") (pintype "passive"))
      (node (ref "R3") (pin "2") (pinfunction "2_2") (pintype "passive"))
    )
    (net (code "15") (name "Net-(I3P-Pad1)") (class "Default")
      (node (ref "I3P") (pin "1") (pinfunction "1_1") (pintype "passive"))
      (node (ref "R6") (pin "2") (pinfunction "2_2") (pintype "passive"))
    )
    (net (code "16") (name "Net-(I4P-Pad1)") (class "Default")
      (node (ref "I4P") (pin "1") (pinfunction "1_1") (pintype "passive"))
      (node (ref "R8") (pin "2") (pinfunction "2_2") (pintype "passive"))
    )
    (net (code "17") (name "Net-(I5P-Pad1)") (class "Default")
      (node (ref "I5P") (pin "1") (pinfunction "1_1") (pintype "passive"))
      (node (ref "R10") (pin "2") (pinfunction "2_2") (pintype "passive"))
    )
    (net (code "18") (name "Net-(I6P-Pad1)") (class "Default")
      (node (ref "I6P") (pin "1") (pinfunction "1_1") (pintype "passive"))
      (node (ref "R17") (pin "2") (pinfunction "2_2") (pintype "passive"))
    )
    (net (code "19") (name "Net-(I7P-Pad1)") (class "Default")
      (node (ref "I7P") (pin "1") (pinfunction "1_1") (pintype "passive"))
      (node (ref "R24") (pin "2") (pinfunction "2_2") (pintype "passive"))
    )
    (net (code "20") (name "Net-(I8P-Pad1)") (class "Default")
      (node (ref "I8P") (pin "1") (pinfunction "1_1") (pintype "passive"))
      (node (ref "R28") (pin "2") (pinfunction "2_2") (pintype "passive"))
    )
    (net (code "21") (name "Net-(I9P-Pad1)") (class "Default")
      (node (ref "I9P") (pin "1") (pinfunction "1_1") (pintype "passive"))
      (node (ref "R34") (pin "2") (pinfunction "2_2") (pintype "passive"))
    )
    (net (code "22") (name "Net-(I10P-Pad1)") (class "Default")
      (node (ref "I10P") (pin "1") (pinfunction "1_1") (pintype "passive"))
      (node (ref "R41") (pin "2") (pinfunction "2_2") (pintype "passive"))
    )
    (net (code "23") (name "Net-(I11P-Pad1)") (class "Default")
      (node (ref "I11P") (pin "1") (pinfunction "1_1") (pintype "passive"))
      (node (ref "R45") (pin "2") (pinfunction "2_2") (pintype "passive"))
    )
    (net (code "24") (name "Net-(I12P-Pad1)") (class "Default")
      (node (ref "I12P") (pin "1") (pinfunction "1_1") (pintype "passive"))
      (node (ref "R47") (pin "2") (pinfunction "2_2") (pintype "passive"))
    )
    (net (code "25") (name "Net-(I13P-Pad1)") (class "Default")
      (node (ref "I13P") (pin "1") (pinfunction "1_1") (pintype "passive"))
      (node (ref "R33") (pin "2") (pinfunction "2_2") (pintype "passive"))
    )
    (net (code "26") (name "Net-(I14P-Pad1)") (class "Default")
      (node (ref "I14P") (pin "1") (pinfunction "1_1") (pintype "passive"))
      (node (ref "R39") (pin "2") (pinfunction "2_2") (pintype "passive"))
    )
    (net (code "27") (name "Net-(O6HC-Pad1)") (class "Default")
      (node (ref "O6HC") (pin "1") (pinfunction "1_1") (pintype "passive"))
      (node (ref "R51") (pin "2") (pinfunction "2_2") (pintype "passive"))
    )
    (net (code "28") (name "Net-(Q1-B)") (class "Default")
      (node (ref "Q1") (pin "1") (pinfunction "B_1") (pintype "passive"))
      (node (ref "R49") (pin "2") (pinfunction "2_2") (pintype "passive"))
    )
    (net (code "29") (name "Net-(Q1-C)") (class "Default")
      (node (ref "Q1") (pin "3") (pinfunction "C_3") (pintype "passive"))
      (node (ref "R50") (pin "2") (pinfunction "2_2") (pintype "passive"))
      (node (ref "R51") (pin "1") (pinfunction "1_1") (pintype "passive"))
    )
    (net (code "30") (name "Net-(Q1-E)") (class "Default")
      (node (ref "C30") (pin "1") (pinfunction "1_1") (pintype "passive"))
      (node (ref "O6-") (pin "1") (pinfunction "1_1") (pintype "passive"))
      (node (ref "Q1") (pin "2") (pinfunction "E_2") (pintype "passive"))
      (node (ref "R48") (pin "2") (pinfunction "2_2") (pintype "passive"))
    )
    (net (code "31") (name "Net-(U1-A)") (class "Default")
      (node (ref "R3") (pin "1") (pinfunction "1_1") (pintype "passive"))
      (node (ref "U1") (pin "1") (pinfunction "A_1") (pintype "passive"))
    )
    (net (code "32") (name "Net-(U1-C)") (class "Default")
      (node (ref "C1") (pin "2") (pinfunction "2_2") (pintype "passive"))
      (node (ref "R1") (pin "2") (pinfunction "2_2") (pintype "passive"))
      (node (ref "U1") (pin "4") (pinfunction "C_4") (pintype "passive"))
      (node (ref "U3") (pin "3") (pinfunction "RA1/AN1/C12IN1-/SEG7/_3") (pintype "bidirectional"))
    )
    (net (code "33") (name "Net-(U1-K)") (class "Default")
      (node (ref "I2N") (pin "1") (pinfunction "1_1") (pintype "passive"))
      (node (ref "U1") (pin "2") (pinfunction "K_2") (pintype "passive"))
    )
    (net (code "34") (name "Net-(U2-A)") (class "Default")
      (node (ref "R4") (pin "1") (pinfunction "1_1") (pintype "passive"))
      (node (ref "U2") (pin "1") (pinfunction "A_1") (pintype "passive"))
    )
    (net (code "35") (name "Net-(U2-C)") (class "Default")
      (node (ref "C2") (pin "2") (pinfunction "2_2") (pintype "passive"))
      (node (ref "R2") (pin "2") (pinfunction "2_2") (pintype "passive"))
      (node (ref "U2") (pin "4") (pinfunction "C_4") (pintype "passive"))
      (node (ref "U3") (pin "2") (pinfunction "RA0/AN0/C12IN0-/C2OUT/SRNQ/~{SS}/VCAP/SEG12_2") (pintype "bidirectional"))
    )
    (net (code "36") (name "Net-(U2-K)") (class "Default")
      (node (ref "I1N") (pin "1") (pinfunction "1_1") (pintype "passive"))
      (node (ref "U2") (pin "2") (pinfunction "K_2") (pintype "passive"))
    )
    (net (code "37") (name "Net-(U3-RA2{slash}AN2{slash}C2IN+{slash}VREF-{slash}DACOUT{slash}COM2{slash})") (class "Default")
      (node (ref "C3") (pin "2") (pinfunction "2_2") (pintype "passive"))
      (node (ref "R5") (pin "2") (pinfunction "2_2") (pintype "passive"))
      (node (ref "U3") (pin "4") (pinfunction "RA2/AN2/C2IN+/VREF-/DACOUT/COM2/_4") (pintype "bidirectional"))
      (node (ref "U4") (pin "4") (pinfunction "C_4") (pintype "passive"))
    )
    (net (code "38") (name "Net-(U3-RA3{slash}AN3{slash}C1IN+{slash}VREF+{slash}COM3{slash}SEG15{slash})") (class "Default")
      (node (ref "C6") (pin "2") (pinfunction "2_2") (pintype "passive"))
      (node (ref "R7") (pin "2") (pinfunction "2_2") (pintype "passive"))
      (node (ref "U3") (pin "5") (pinfunction "RA3/AN3/C1IN+/VREF+/COM3/SEG15/_5") (pintype "bidirectional"))
      (node (ref "U5") (pin "4") (pinfunction "C_4") (pintype "passive"))
    )
    (net (code "39") (name "Net-(U3-RA4{slash}C1OUT{slash}CPS6{slash}T0CKI{slash}SRQ{slash}CCP5{slash}SEG4)") (class "Default")
      (node (ref "C8") (pin "2") (pinfunction "2_2") (pintype "passive"))
      (node (ref "R9") (pin "2") (pinfunction "2_2") (pintype "passive"))
      (node (ref "U3") (pin "6") (pinfunction "RA4/C1OUT/CPS6/T0CKI/SRQ/CCP5/SEG4_6") (pintype "bidirectional"))
      (node (ref "U6") (pin "4") (pinfunction "C_4") (pintype "passive"))
    )
    (net (code "40") (name "Net-(U3-RA5{slash}AN4{slash}C2OUT{slash}CPS7{slash}SRNQ{slash}~{SS}{slash}VCAP{slash}SEG5)") (class "Default")
      (node (ref "C14") (pin "2") (pinfunction "2_2") (pintype "passive"))
      (node (ref "R15") (pin "2") (pinfunction "2_2") (pintype "passive"))
      (node (ref "U3") (pin "7") (pinfunction "RA5/AN4/C2OUT/CPS7/SRNQ/~{SS}/VCAP/SEG5_7") (pintype "bidirectional"))
      (node (ref "U9") (pin "4") (pinfunction "C_4") (pintype "passive"))
    )
    (net (code "41") (name "Net-(U3-RA6{slash}OSC2{slash}CLKOUT{slash}VCAP{slash}SEG1)") (class "Default")
      (node (ref "C5") (pin "1") (pinfunction "1_1") (pintype "passive"))
      (node (ref "U3") (pin "10") (pinfunction "RA6/OSC2/CLKOUT/VCAP/SEG1_10") (pintype "bidirectional"))
      (node (ref "Y1") (pin "1") (pinfunction "OSC1_1") (pintype "passive"))
    )
    (net (code "42") (name "Net-(U3-RA7{slash}OSC1{slash}CLKIN{slash}SEG2)") (class "Default")
      (node (ref "C4") (pin "2") (pinfunction "2_2") (pintype "passive"))
      (node (ref "U3") (pin "9") (pinfunction "RA7/OSC1/CLKIN/SEG2_9") (pintype "bidirectional"))
      (node (ref "Y1") (pin "2") (pinfunction "OSC2_2") (pintype "passive"))
    )
    (net (code "43") (name "Net-(U3-RC0{slash}T1OSO{slash}T1CKI{slash}P2B)") (class "Default")
      (node (ref "R14") (pin "1") (pinfunction "1_1") (pintype "passive"))
      (node (ref "U3") (pin "11") (pinfunction "RC0/T1OSO/T1CKI/P2B_11") (pintype "bidirectional"))
    )
    (net (code "44") (name "Net-(U3-RC1{slash}T1OSI{slash}CCP2{slash}P2A)") (class "Default")
      (node (ref "R12") (pin "1") (pinfunction "1_1") (pintype "passive"))
      (node (ref "U3") (pin "12") (pinfunction "RC1/T1OSI/CCP2/P2A_12") (pintype "bidirectional"))
    )
    (net (code "45") (name "Net-(U3-RC2{slash}CCP1{slash}P1A{slash}SEG3)") (class "Default")
      (node (ref "R20") (pin "1") (pinfunction "1_1") (pintype "passive"))
      (node (ref "U3") (pin "13") (pinfunction "RC2/CCP1/P1A/SEG3_13") (pintype "bidirectional"))
    )
    (net (code "46") (name "Net-(U3-RC3{slash}SCK{slash}SCL{slash}SEG6)") (class "Default")
      (node (ref "R23") (pin "2") (pinfunction "2_2") (pintype "passive"))
      (node (ref "SCL") (pin "1") (pinfunction "1_1") (pintype "passive"))
      (node (ref "U3") (pin "14") (pinfunction "RC3/SCK/SCL/SEG6_14") (pintype "bidirectional"))
    )
    (net (code "47") (name "Net-(U3-RC4{slash}SDI{slash}SDA{slash}T1G{slash}SEG11)") (class "Default")
      (node (ref "R22") (pin "2") (pinfunction "2_2") (pintype "passive"))
      (node (ref "SDA") (pin "1") (pinfunction "1_1") (pintype "passive"))
      (node (ref "U3") (pin "15") (pinfunction "RC4/SDI/SDA/T1G/SEG11_15") (pintype "bidirectional"))
    )
    (net (code "48") (name "Net-(U3-RC5{slash}SDO{slash}SEG10)") (class "Default")
      (node (ref "R46") (pin "1") (pinfunction "1_1") (pintype "passive"))
      (node (ref "U3") (pin "16") (pinfunction "RC5/SDO/SEG10_16") (pintype "bidirectional"))
    )
    (net (code "49") (name "Net-(U3-RC6{slash}TX{slash}CK{slash}CCP3{slash}P3A{slash}SEG9)") (class "Default")
      (node (ref "R36") (pin "1") (pinfunction "1_1") (pintype "passive"))
      (node (ref "U3") (pin "17") (pinfunction "RC6/TX/CK/CCP3/P3A/SEG9_17") (pintype "bidirectional"))
    )
    (net (code "50") (name "Net-(U3-RC7{slash}RX{slash}DT{slash}P3B{slash}SEG8)") (class "Default")
      (node (ref "R29") (pin "1") (pinfunction "1_1") (pintype "passive"))
      (node (ref "U3") (pin "18") (pinfunction "RC7/RX/DT/P3B/SEG8_18") (pintype "bidirectional"))
    )
    (net (code "51") (name "Net-(U3-RE3{slash}~{MCLR}{slash}VPP)") (class "Default")
      (node (ref "MCLR") (pin "1") (pinfunction "1_1") (pintype "passive"))
      (node (ref "U3") (pin "1") (pinfunction "RE3/~{MCLR}/VPP_1") (pintype "input"))
    )
    (net (code "52") (name "Net-(U4-A)") (class "Default")
      (node (ref "R6") (pin "1") (pinfunction "1_1") (pintype "passive"))
      (node (ref "U4") (pin "1") (pinfunction "A_1") (pintype "passive"))
    )
    (net (code "53") (name "Net-(U4-K)") (class "Default")
      (node (ref "I3N") (pin "1") (pinfunction "1_1") (pintype "passive"))
      (node (ref "U4") (pin "2") (pinfunction "K_2") (pintype "passive"))
    )
    (net (code "54") (name "Net-(U5-A)") (class "Default")
      (node (ref "R8") (pin "1") (pinfunction "1_1") (pintype "passive"))
      (node (ref "U5") (pin "1") (pinfunction "A_1") (pintype "passive"))
    )
    (net (code "55") (name "Net-(U5-K)") (class "Default")
      (node (ref "I4N") (pin "1") (pinfunction "1_1") (pintype "passive"))
      (node (ref "U5") (pin "2") (pinfunction "K_2") (pintype "passive"))
    )
    (net (code "56") (name "Net-(U6-A)") (class "Default")
      (node (ref "R10") (pin "1") (pinfunction "1_1") (pintype "passive"))
      (node (ref "U6") (pin "1") (pinfunction "A_1") (pintype "passive"))
    )
    (net (code "57") (name "Net-(U6-K)") (class "Default")
      (node (ref "I5N") (pin "1") (pinfunction "1_1") (pintype "passive"))
      (node (ref "U6") (pin "2") (pinfunction "K_2") (pintype "passive"))
    )
    (net (code "58") (name "Net-(U7-A)") (class "Default")
      (node (ref "R12") (pin "2") (pinfunction "2_2") (pintype "passive"))
      (node (ref "U7") (pin "1") (pinfunction "A_1") (pintype "passive"))
    )
    (net (code "59") (name "Net-(U7-C)") (class "Default")
      (node (ref "C7") (pin "1") (pinfunction "1_1") (pintype "passive"))
      (node (ref "O2P") (pin "1") (pinfunction "1_1") (pintype "passive"))
      (node (ref "R11") (pin "2") (pinfunction "2_2") (pintype "passive"))
      (node (ref "U7") (pin "4") (pinfunction "C_4") (pintype "passive"))
    )
    (net (code "60") (name "Net-(U7-E)") (class "Default")
      (node (ref "C12") (pin "2") (pinfunction "2_2") (pintype "passive"))
      (node (ref "O2N") (pin "1") (pinfunction "1_1") (pintype "passive"))
      (node (ref "R16") (pin "1") (pinfunction "1_1") (pintype "passive"))
      (node (ref "U7") (pin "3") (pinfunction "E_3") (pintype "passive"))
    )
    (net (code "61") (name "Net-(U8-A)") (class "Default")
      (node (ref "R14") (pin "2") (pinfunction "2_2") (pintype "passive"))
      (node (ref "U8") (pin "1") (pinfunction "A_1") (pintype "passive"))
    )
    (net (code "62") (name "Net-(U8-C)") (class "Default")
      (node (ref "C9") (pin "1") (pinfunction "1_1") (pintype "passive"))
      (node (ref "O1P") (pin "1") (pinfunction "1_1") (pintype "passive"))
      (node (ref "R13") (pin "2") (pinfunction "2_2") (pintype "passive"))
      (node (ref "U8") (pin "4") (pinfunction "C_4") (pintype "passive"))
    )
    (net (code "63") (name "Net-(U8-E)") (class "Default")
      (node (ref "C13") (pin "2") (pinfunction "2_2") (pintype "passive"))
      (node (ref "O1N") (pin "1") (pinfunction "1_1") (pintype "passive"))
      (node (ref "R18") (pin "1") (pinfunction "1_1") (pintype "passive"))
      (node (ref "U8") (pin "3") (pinfunction "E_3") (pintype "passive"))
    )
    (net (code "64") (name "Net-(U9-A)") (class "Default")
      (node (ref "R17") (pin "1") (pinfunction "1_1") (pintype "passive"))
      (node (ref "U9") (pin "1") (pinfunction "A_1") (pintype "passive"))
    )
    (net (code "65") (name "Net-(U9-K)") (class "Default")
      (node (ref "I6N") (pin "1") (pinfunction "1_1") (pintype "passive"))
      (node (ref "U9") (pin "2") (pinfunction "K_2") (pintype "passive"))
    )
    (net (code "66") (name "Net-(U10-A)") (class "Default")
      (node (ref "R20") (pin "2") (pinfunction "2_2") (pintype "passive"))
      (node (ref "U10") (pin "1") (pinfunction "A_1") (pintype "passive"))
    )
    (net (code "67") (name "Net-(U10-C)") (class "Default")
      (node (ref "C15") (pin "1") (pinfunction "1_1") (pintype "passive"))
      (node (ref "O3P") (pin "1") (pinfunction "1_1") (pintype "passive"))
      (node (ref "R19") (pin "2") (pinfunction "2_2") (pintype "passive"))
      (node (ref "U10") (pin "4") (pinfunction "C_4") (pintype "passive"))
    )
    (net (code "68") (name "Net-(U10-E)") (class "Default")
      (node (ref "C17") (pin "2") (pinfunction "2_2") (pintype "passive"))
      (node (ref "O3N") (pin "1") (pinfunction "1_1") (pintype "passive"))
      (node (ref "R25") (pin "1") (pinfunction "1_1") (pintype "passive"))
      (node (ref "U10") (pin "3") (pinfunction "E_3") (pintype "passive"))
    )
    (net (code "69") (name "Net-(U11-A)") (class "Default")
      (node (ref "R24") (pin "1") (pinfunction "1_1") (pintype "passive"))
      (node (ref "U11") (pin "1") (pinfunction "A_1") (pintype "passive"))
    )
    (net (code "70") (name "Net-(U11-C)") (class "Default")
      (node (ref "C16") (pin "2") (pinfunction "2_2") (pintype "passive"))
      (node (ref "R21") (pin "2") (pinfunction "2_2") (pintype "passive"))
      (node (ref "U11") (pin "4") (pinfunction "C_4") (pintype "passive"))
      (node (ref "U3") (pin "21") (pinfunction "RB0/AN12/CPS0/CCP4/SRI/INT/SEG0_21") (pintype "bidirectional"))
    )
    (net (code "71") (name "Net-(U11-K)") (class "Default")
      (node (ref "I7N") (pin "1") (pinfunction "1_1") (pintype "passive"))
      (node (ref "U11") (pin "2") (pinfunction "K_2") (pintype "passive"))
    )
    (net (code "72") (name "Net-(U12-A)") (class "Default")
      (node (ref "R28") (pin "1") (pinfunction "1_1") (pintype "passive"))
      (node (ref "U12") (pin "1") (pinfunction "A_1") (pintype "passive"))
    )
    (net (code "73") (name "Net-(U12-C)") (class "Default")
      (node (ref "C19") (pin "2") (pinfunction "2_2") (pintype "passive"))
      (node (ref "R26") (pin "2") (pinfunction "2_2") (pintype "passive"))
      (node (ref "U12") (pin "4") (pinfunction "C_4") (pintype "passive"))
      (node (ref "U3") (pin "22") (pinfunction "RB1/AN10/C12IN3-/CPS1/P1C/VLCD1_22") (pintype "bidirectional"))
    )
    (net (code "74") (name "Net-(U12-K)") (class "Default")
      (node (ref "I8N") (pin "1") (pinfunction "1_1") (pintype "passive"))
      (node (ref "U12") (pin "2") (pinfunction "K_2") (pintype "passive"))
    )
    (net (code "75") (name "Net-(U13-A)") (class "Default")
      (node (ref "R29") (pin "2") (pinfunction "2_2") (pintype "passive"))
      (node (ref "U13") (pin "1") (pinfunction "A_1") (pintype "passive"))
    )
    (net (code "76") (name "Net-(U13-C)") (class "Default")
      (node (ref "C18") (pin "1") (pinfunction "1_1") (pintype "passive"))
      (node (ref "O4P") (pin "1") (pinfunction "1_1") (pintype "passive"))
      (node (ref "R27") (pin "2") (pinfunction "2_2") (pintype "passive"))
      (node (ref "U13") (pin "4") (pinfunction "C_4") (pintype "passive"))
    )
    (net (code "77") (name "Net-(U13-E)") (class "Default")
      (node (ref "C20") (pin "2") (pinfunction "2_2") (pintype "passive"))
      (node (ref "O4N") (pin "1") (pinfunction "1_1") (pintype "passive"))
      (node (ref "R30") (pin "1") (pinfunction "1_1") (pintype "passive"))
      (node (ref "U13") (pin "3") (pinfunction "E_3") (pintype "passive"))
    )
    (net (code "78") (name "Net-(U14-A)") (class "Default")
      (node (ref "R33") (pin "1") (pinfunction "1_1") (pintype "passive"))
      (node (ref "U14") (pin "1") (pinfunction "A_1") (pintype "passive"))
    )
    (net (code "79") (name "Net-(U14-C)") (class "Default")
      (node (ref "C21") (pin "2") (pinfunction "2_2") (pintype "passive"))
      (node (ref "R31") (pin "2") (pinfunction "2_2") (pintype "passive"))
      (node (ref "U14") (pin "4") (pinfunction "C_4") (pintype "passive"))
      (node (ref "U3") (pin "27") (pinfunction "RB6/ICSPCLK/ICDCLK/SEG14_27") (pintype "bidirectional"))
    )
    (net (code "80") (name "Net-(U14-E)") (class "Default")
      (node (ref "C21") (pin "1") (pinfunction "1_1") (pintype "passive"))
      (node (ref "U14") (pin "3") (pinfunction "E_3") (pintype "passive"))
    )
    (net (code "81") (name "Net-(U14-K)") (class "Default")
      (node (ref "I13N") (pin "1") (pinfunction "1_1") (pintype "passive"))
      (node (ref "U14") (pin "2") (pinfunction "K_2") (pintype "passive"))
    )
    (net (code "82") (name "Net-(U15-A)") (class "Default")
      (node (ref "R34") (pin "1") (pinfunction "1_1") (pintype "passive"))
      (node (ref "U15") (pin "1") (pinfunction "A_1") (pintype "passive"))
    )
    (net (code "83") (name "Net-(U15-C)") (class "Default")
      (node (ref "C22") (pin "2") (pinfunction "2_2") (pintype "passive"))
      (node (ref "R32") (pin "2") (pinfunction "2_2") (pintype "passive"))
      (node (ref "U15") (pin "4") (pinfunction "C_4") (pintype "passive"))
      (node (ref "U3") (pin "23") (pinfunction "RB2/AN8/CPS2/P1B/VLCD2_23") (pintype "bidirectional"))
    )
    (net (code "84") (name "Net-(U15-K)") (class "Default")
      (node (ref "I9N") (pin "1") (pinfunction "1_1") (pintype "passive"))
      (node (ref "U15") (pin "2") (pinfunction "K_2") (pintype "passive"))
    )
    (net (code "85") (name "Net-(U16-A)") (class "Default")
      (node (ref "R36") (pin "2") (pinfunction "2_2") (pintype "passive"))
      (node (ref "U16") (pin "1") (pinfunction "A_1") (pintype "passive"))
    )
    (net (code "86") (name "Net-(U16-C)") (class "Default")
      (node (ref "C23") (pin "1") (pinfunction "1_1") (pintype "passive"))
      (node (ref "O5P") (pin "1") (pinfunction "1_1") (pintype "passive"))
      (node (ref "R35") (pin "2") (pinfunction "2_2") (pintype "passive"))
      (node (ref "U16") (pin "4") (pinfunction "C_4") (pintype "passive"))
    )
    (net (code "87") (name "Net-(U16-E)") (class "Default")
      (node (ref "C24") (pin "2") (pinfunction "2_2") (pintype "passive"))
      (node (ref "O5N") (pin "1") (pinfunction "1_1") (pintype "passive"))
      (node (ref "R40") (pin "1") (pinfunction "1_1") (pintype "passive"))
      (node (ref "U16") (pin "3") (pinfunction "E_3") (pintype "passive"))
    )
    (net (code "88") (name "Net-(U17-A)") (class "Default")
      (node (ref "R39") (pin "1") (pinfunction "1_1") (pintype "passive"))
      (node (ref "U17") (pin "1") (pinfunction "A_1") (pintype "passive"))
    )
    (net (code "89") (name "Net-(U17-C)") (class "Default")
      (node (ref "C25") (pin "2") (pinfunction "2_2") (pintype "passive"))
      (node (ref "R37") (pin "2") (pinfunction "2_2") (pintype "passive"))
      (node (ref "U17") (pin "4") (pinfunction "C_4") (pintype "passive"))
      (node (ref "U3") (pin "28") (pinfunction "RB7/ICSPDAT/ICDDAT/SEG13_28") (pintype "bidirectional"))
    )
    (net (code "90") (name "Net-(U17-E)") (class "Default")
      (node (ref "C25") (pin "1") (pinfunction "1_1") (pintype "passive"))
      (node (ref "U17") (pin "3") (pinfunction "E_3") (pintype "passive"))
    )
    (net (code "91") (name "Net-(U17-K)") (class "Default")
      (node (ref "I14N") (pin "1") (pinfunction "1_1") (pintype "passive"))
      (node (ref "U17") (pin "2") (pinfunction "K_2") (pintype "passive"))
    )
    (net (code "92") (name "Net-(U18-A)") (class "Default")
      (node (ref "R41") (pin "1") (pinfunction "1_1") (pintype "passive"))
      (node (ref "U18") (pin "1") (pinfunction "A_1") (pintype "passive"))
    )
    (net (code "93") (name "Net-(U18-C)") (class "Default")
      (node (ref "C26") (pin "2") (pinfunction "2_2") (pintype "passive"))
      (node (ref "R38") (pin "2") (pinfunction "2_2") (pintype "passive"))
      (node (ref "U18") (pin "4") (pinfunction "C_4") (pintype "passive"))
      (node (ref "U3") (pin "24") (pinfunction "RB3/AN9/C12IN2-/CPS3/CCP2/P2A/VLCD3_24") (pintype "bidirectional"))
    )
    (net (code "94") (name "Net-(U18-K)") (class "Default")
      (node (ref "I10N") (pin "1") (pinfunction "1_1") (pintype "passive"))
      (node (ref "U18") (pin "2") (pinfunction "K_2") (pintype "passive"))
    )
    (net (code "95") (name "Net-(U19-A)") (class "Default")
      (node (ref "R45") (pin "1") (pinfunction "1_1") (pintype "passive"))
      (node (ref "U19") (pin "1") (pinfunction "A_1") (pintype "passive"))
    )
    (net (code "96") (name "Net-(U19-C)") (class "Default")
      (node (ref "C28") (pin "2") (pinfunction "2_2") (pintype "passive"))
      (node (ref "R42") (pin "2") (pinfunction "2_2") (pintype "passive"))
      (node (ref "U19") (pin "4") (pinfunction "C_4") (pintype "passive"))
      (node (ref "U3") (pin "25") (pinfunction "RB4/AN11/CPS4/P1D/COM0_25") (pintype "bidirectional"))
    )
    (net (code "97") (name "Net-(U19-K)") (class "Default")
      (node (ref "I11N") (pin "1") (pinfunction "1_1") (pintype "passive"))
      (node (ref "U19") (pin "2") (pinfunction "K_2") (pintype "passive"))
    )
    (net (code "98") (name "Net-(U20-A)") (class "Default")
      (node (ref "R46") (pin "2") (pinfunction "2_2") (pintype "passive"))
      (node (ref "U20") (pin "1") (pinfunction "A_1") (pintype "passive"))
    )
    (net (code "99") (name "Net-(U20-C)") (class "Default")
      (node (ref "C27") (pin "1") (pinfunction "1_1") (pintype "passive"))
      (node (ref "O6P") (pin "1") (pinfunction "1_1") (pintype "passive"))
      (node (ref "R43") (pin "2") (pinfunction "2_2") (pintype "passive"))
      (node (ref "U20") (pin "4") (pinfunction "C_4") (pintype "passive"))
    )
    (net (code "100") (name "Net-(U20-E)") (class "Default")
      (node (ref "C30") (pin "2") (pinfunction "2_2") (pintype "passive"))
      (node (ref "O6N") (pin "1") (pinfunction "1_1") (pintype "passive"))
      (node (ref "R48") (pin "1") (pinfunction "1_1") (pintype "passive"))
      (node (ref "R49") (pin "1") (pinfunction "1_1") (pintype "passive"))
      (node (ref "U20") (pin "3") (pinfunction "E_3") (pintype "passive"))
    )
    (net (code "101") (name "Net-(U21-A)") (class "Default")
      (node (ref "R47") (pin "1") (pinfunction "1_1") (pintype "passive"))
      (node (ref "U21") (pin "1") (pinfunction "A_1") (pintype "passive"))
    )
    (net (code "102") (name "Net-(U21-C)") (class "Default")
      (node (ref "C29") (pin "2") (pinfunction "2_2") (pintype "passive"))
      (node (ref "R44") (pin "2") (pinfunction "2_2") (pintype "passive"))
      (node (ref "U21") (pin "4") (pinfunction "C_4") (pintype "passive"))
      (node (ref "U3") (pin "26") (pinfunction "RB5/AN13/CPS5/P2B/CCP3/P3AT1G/COM1_26") (pintype "bidirectional"))
    )
    (net (code "103") (name "Net-(U21-K)") (class "Default")
      (node (ref "I12N") (pin "1") (pinfunction "1_1") (pintype "passive"))
      (node (ref "U21") (pin "2") (pinfunction "K_2") (pintype "passive"))
    )
    (net (code "104") (name "VCC") (class "Default")
      (node (ref "+5V") (pin "1") (pinfunction "1_1") (pintype "passive"))
      (node (ref "C10") (pin "2") (pinfunction "2_2") (pintype "passive"))
      (node (ref "C11") (pin "2") (pinfunction "2_2") (pintype "passive"))
      (node (ref "R1") (pin "1") (pinfunction "1_1") (pintype "passive"))
      (node (ref "R15") (pin "1") (pinfunction "1_1") (pintype "passive"))
      (node (ref "R2") (pin "1") (pinfunction "1_1") (pintype "passive"))
      (node (ref "R21") (pin "1") (pinfunction "1_1") (pintype "passive"))
      (node (ref "R22") (pin "1") (pinfunction "1_1") (pintype "passive"))
      (node (ref "R23") (pin "1") (pinfunction "1_1") (pintype "passive"))
      (node (ref "R26") (pin "1") (pinfunction "1_1") (pintype "passive"))
      (node (ref "R31") (pin "1") (pinfunction "1_1") (pintype "passive"))
      (node (ref "R32") (pin "1") (pinfunction "1_1") (pintype "passive"))
      (node (ref "R37") (pin "1") (pinfunction "1_1") (pintype "passive"))
      (node (ref "R38") (pin "1") (pinfunction "1_1") (pintype "passive"))
      (node (ref "R42") (pin "1") (pinfunction "1_1") (pintype "passive"))
      (node (ref "R44") (pin "1") (pinfunction "1_1") (pintype "passive"))
      (node (ref "R5") (pin "1") (pinfunction "1_1") (pintype "passive"))
      (node (ref "R7") (pin "1") (pinfunction "1_1") (pintype "passive"))
      (node (ref "R9") (pin "1") (pinfunction "1_1") (pintype "passive"))
      (node (ref "U3") (pin "20") (pinfunction "VDD_20") (pintype "power_in"))
    )
  )
)
